# NST-28037B.net
KiCad netlist of a schematic drawn in EAGLE
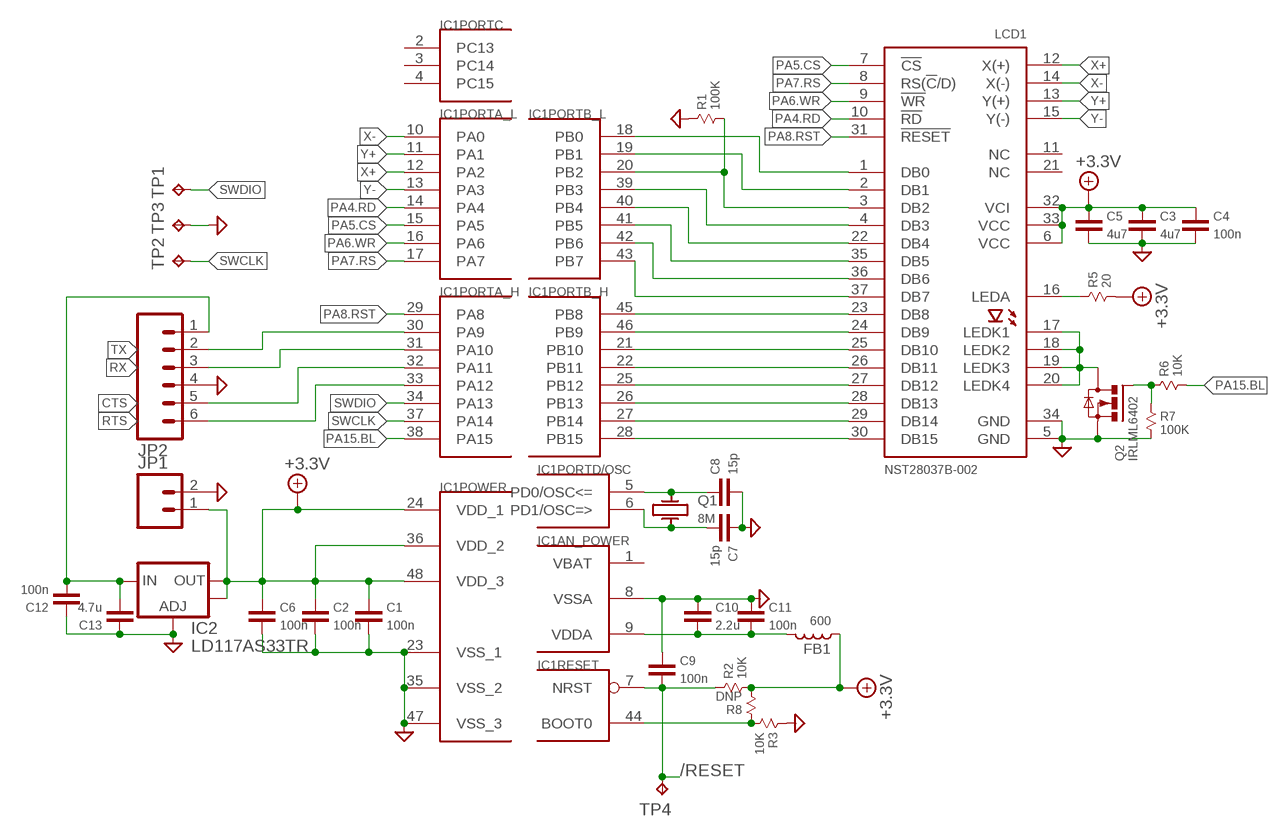
[diagram p0: schematic, sheet 1]

(export (version "E")
  (design (tool "Eeschema 10.0.6"))
  (components
    (comp (ref "C1")
      (value "100n")
      (footprint "eagle-import:0603")
      (libsource (lib "eagle-import") (part "CAP-0603"))
    )
    (comp (ref "C2")
      (value "100n")
      (footprint "eagle-import:0603")
      (libsource (lib "eagle-import") (part "CAP-0603"))
    )
    (comp (ref "C3")
      (value "4u7")
      (footprint "eagle-import:0603")
      (libsource (lib "eagle-import") (part "CAP-0603"))
    )
    (comp (ref "C4")
      (value "100n")
      (footprint "eagle-import:0603")
      (libsource (lib "eagle-import") (part "CAP-0603"))
    )
    (comp (ref "C5")
      (value "4u7")
      (footprint "eagle-import:0603")
      (libsource (lib "eagle-import") (part "CAP-0603"))
    )
    (comp (ref "C6")
      (value "100n")
      (footprint "eagle-import:0603")
      (libsource (lib "eagle-import") (part "CAP-0603"))
    )
    (comp (ref "C7")
      (value "15p")
      (footprint "eagle-import:0603")
      (libsource (lib "eagle-import") (part "CAP-0603"))
    )
    (comp (ref "C8")
      (value "15p")
      (footprint "eagle-import:0603")
      (libsource (lib "eagle-import") (part "CAP-0603"))
    )
    (comp (ref "C9")
      (value "100n")
      (footprint "eagle-import:0603")
      (libsource (lib "eagle-import") (part "CAP-0603"))
    )
    (comp (ref "C10")
      (value "2.2u")
      (footprint "eagle-import:0603")
      (libsource (lib "eagle-import") (part "CAP-0603"))
    )
    (comp (ref "C11")
      (value "100n")
      (footprint "eagle-import:0603")
      (libsource (lib "eagle-import") (part "CAP-0603"))
    )
    (comp (ref "C12")
      (value "100n")
      (footprint "eagle-import:0603")
      (libsource (lib "eagle-import") (part "CAP-0603"))
    )
    (comp (ref "C13")
      (value "4.7u")
      (footprint "eagle-import:0603")
      (libsource (lib "eagle-import") (part "CAP-0603"))
    )
    (comp (ref "FB1")
      (value "600")
      (footprint "eagle-import:0603")
      (libsource (lib "eagle-import") (part "INDUCTOR-0603"))
    )
    (comp (ref "IC1")
      (value "STM32F10XCXT6")
      (footprint "eagle-import:TQFP48")
      (libsource (lib "eagle-import") (part "STM32F10XCXT6"))
    )
    (comp (ref "IC2")
      (value "LD117AS33TR")
      (footprint "eagle-import:SOT223")
      (libsource (lib "eagle-import") (part "LD117A?S33TR"))
    )
    (comp (ref "JP1")
      (value "M02PTH")
      (footprint "eagle-import:1X02")
      (libsource (lib "eagle-import") (part "M02PTH"))
    )
    (comp (ref "JP2")
      (value "M06SIP")
      (footprint "eagle-import:1X06")
      (libsource (lib "eagle-import") (part "M06SIP"))
    )
    (comp (ref "LCD1")
      (value "NST28037B-002")
      (footprint "eagle-import:NST28037B-002")
      (libsource (lib "eagle-import") (part "NST28037B-002"))
    )
    (comp (ref "Q1")
      (value "8M")
      (footprint "eagle-import:KX-9A")
      (libsource (lib "eagle-import") (part "CRYSTAL-KX-9A"))
    )
    (comp (ref "Q2")
      (value "IRLML6402")
      (footprint "eagle-import:SOT-23")
      (libsource (lib "eagle-import") (part "MOSFET-N-SOT23"))
    )
    (comp (ref "R1")
      (value "100K")
      (footprint "eagle-import:0603")
      (libsource (lib "eagle-import") (part "RESISTOR-0603"))
    )
    (comp (ref "R2")
      (value "10K")
      (footprint "eagle-import:0603")
      (libsource (lib "eagle-import") (part "RESISTOR-0603"))
    )
    (comp (ref "R3")
      (value "10K")
      (footprint "eagle-import:0603")
      (libsource (lib "eagle-import") (part "RESISTOR-0603"))
    )
    (comp (ref "R5")
      (value "20")
      (footprint "eagle-import:0805")
      (libsource (lib "eagle-import") (part "RESISTOR-0805"))
    )
    (comp (ref "R6")
      (value "10K")
      (footprint "eagle-import:0603")
      (libsource (lib "eagle-import") (part "RESISTOR-0603"))
    )
    (comp (ref "R7")
      (value "100K")
      (footprint "eagle-import:0603")
      (libsource (lib "eagle-import") (part "RESISTOR-0603"))
    )
    (comp (ref "R8")
      (value "DNP")
      (footprint "eagle-import:0603")
      (libsource (lib "eagle-import") (part "RESISTOR-0603"))
    )
    (comp (ref "TP1")
      (value "TPTP12R")
      (footprint "eagle-import:TP12R")
      (libsource (lib "eagle-import") (part "TPTP12R"))
    )
    (comp (ref "TP2")
      (value "TPTP12R")
      (footprint "eagle-import:TP12R")
      (libsource (lib "eagle-import") (part "TPTP12R"))
    )
    (comp (ref "TP3")
      (value "TPTP12R")
      (footprint "eagle-import:TP12R")
      (libsource (lib "eagle-import") (part "TPTP12R"))
    )
    (comp (ref "TP4")
      (value "TPTP12R")
      (footprint "eagle-import:TP12R")
      (libsource (lib "eagle-import") (part "TPTP12R"))
    )
  )
  (nets
    (net (code "1") (name "+3.3V") (class "Default")
      (node (ref "C1") (pin "2") (pinfunction "2_2") (pintype "passive"))
      (node (ref "C2") (pin "2") (pinfunction "2_2") (pintype "passive"))
      (node (ref "C3") (pin "2") (pinfunction "2_2") (pintype "passive"))
      (node (ref "C4") (pin "2") (pinfunction "2_2") (pintype "passive"))
      (node (ref "C5") (pin "2") (pinfunction "2_2") (pintype "passive"))
      (node (ref "C6") (pin "2") (pinfunction "2_2") (pintype "passive"))
      (node (ref "FB1") (pin "1") (pinfunction "1_1") (pintype "passive"))
      (node (ref "IC1") (pin "24") (pinfunction "VDD_1_24") (pintype "power_in"))
      (node (ref "IC1") (pin "36") (pinfunction "VDD_2_36") (pintype "power_in"))
      (node (ref "IC1") (pin "48") (pinfunction "VDD_3_48") (pintype "power_in"))
      (node (ref "IC2") (pin "2") (pinfunction "OUT_2") (pintype "passive"))
      (node (ref "IC2") (pin "4") (pinfunction "OUT_4") (pintype "passive"))
      (node (ref "JP1") (pin "1") (pinfunction "1_1") (pintype "passive"))
      (node (ref "LCD1") (pin "32") (pinfunction "VCI_32") (pintype "power_in"))
      (node (ref "LCD1") (pin "33") (pinfunction "VCC_33") (pintype "power_in"))
      (node (ref "LCD1") (pin "6") (pinfunction "VCC_6") (pintype "power_in"))
      (node (ref "R2") (pin "2") (pinfunction "2_2") (pintype "passive"))
      (node (ref "R5") (pin "2") (pinfunction "2_2") (pintype "passive"))
      (node (ref "R8") (pin "2") (pinfunction "2_2") (pintype "passive"))
    )
    (net (code "2") (name "/VBAT") (class "Default")
      (node (ref "IC1") (pin "1") (pinfunction "VBAT_1") (pintype "power_in"))
    )
    (net (code "3") (name "/{slash}RESET") (class "Default")
      (node (ref "C9") (pin "1") (pinfunction "1_1") (pintype "passive"))
      (node (ref "IC1") (pin "7") (pinfunction "NRST_7") (pintype "input"))
      (node (ref "R2") (pin "1") (pinfunction "1_1") (pintype "passive"))
      (node (ref "TP4") (pin "TP") (pinfunction "TP_TP") (pintype "input"))
    )
    (net (code "4") (name "CTS") (class "Default")
      (node (ref "IC1") (pin "32") (pinfunction "PA11_32") (pintype "bidirectional"))
      (node (ref "JP2") (pin "5") (pinfunction "5_5") (pintype "passive"))
    )
    (net (code "5") (name "GND") (class "Default")
      (node (ref "C1") (pin "1") (pinfunction "1_1") (pintype "passive"))
      (node (ref "C10") (pin "2") (pinfunction "2_2") (pintype "passive"))
      (node (ref "C11") (pin "2") (pinfunction "2_2") (pintype "passive"))
      (node (ref "C12") (pin "2") (pinfunction "2_2") (pintype "passive"))
      (node (ref "C13") (pin "2") (pinfunction "2_2") (pintype "passive"))
      (node (ref "C2") (pin "1") (pinfunction "1_1") (pintype "passive"))
      (node (ref "C3") (pin "1") (pinfunction "1_1") (pintype "passive"))
      (node (ref "C4") (pin "1") (pinfunction "1_1") (pintype "passive"))
      (node (ref "C5") (pin "1") (pinfunction "1_1") (pintype "passive"))
      (node (ref "C6") (pin "1") (pinfunction "1_1") (pintype "passive"))
      (node (ref "C7") (pin "2") (pinfunction "2_2") (pintype "passive"))
      (node (ref "C8") (pin "1") (pinfunction "1_1") (pintype "passive"))
      (node (ref "C9") (pin "2") (pinfunction "2_2") (pintype "passive"))
      (node (ref "IC1") (pin "23") (pinfunction "VSS_1_23") (pintype "power_in"))
      (node (ref "IC1") (pin "35") (pinfunction "VSS_2_35") (pintype "power_in"))
      (node (ref "IC1") (pin "47") (pinfunction "VSS_3_47") (pintype "power_in"))
      (node (ref "IC1") (pin "8") (pinfunction "VSSA_8") (pintype "power_in"))
      (node (ref "IC2") (pin "1") (pinfunction "ADJ_1") (pintype "input"))
      (node (ref "JP1") (pin "2") (pinfunction "2_2") (pintype "passive"))
      (node (ref "JP2") (pin "4") (pinfunction "4_4") (pintype "passive"))
      (node (ref "LCD1") (pin "34") (pinfunction "GND_34") (pintype "power_in"))
      (node (ref "LCD1") (pin "5") (pinfunction "GND_5") (pintype "power_in"))
      (node (ref "Q2") (pin "2") (pinfunction "S_2") (pintype "passive"))
      (node (ref "R1") (pin "1") (pinfunction "1_1") (pintype "passive"))
      (node (ref "R3") (pin "1") (pinfunction "1_1") (pintype "passive"))
      (node (ref "R7") (pin "2") (pinfunction "2_2") (pintype "passive"))
      (node (ref "TP3") (pin "TP") (pinfunction "TP_TP") (pintype "input"))
    )
    (net (code "6") (name "Net-(IC1A-VDDA)") (class "Default")
      (node (ref "C10") (pin "1") (pinfunction "1_1") (pintype "passive"))
      (node (ref "C11") (pin "1") (pinfunction "1_1") (pintype "passive"))
      (node (ref "FB1") (pin "2") (pinfunction "2_2") (pintype "passive"))
      (node (ref "IC1") (pin "9") (pinfunction "VDDA_9") (pintype "power_in"))
    )
    (net (code "7") (name "Net-(IC1D-PB8)") (class "Default")
      (node (ref "IC1") (pin "45") (pinfunction "PB8_45") (pintype "bidirectional"))
      (node (ref "LCD1") (pin "23") (pinfunction "DB8_23") (pintype "bidirectional"))
    )
    (net (code "8") (name "Net-(IC1D-PB9)") (class "Default")
      (node (ref "IC1") (pin "46") (pinfunction "PB9_46") (pintype "bidirectional"))
      (node (ref "LCD1") (pin "24") (pinfunction "DB9_24") (pintype "bidirectional"))
    )
    (net (code "9") (name "Net-(IC1D-PB10)") (class "Default")
      (node (ref "IC1") (pin "21") (pinfunction "PB10_21") (pintype "bidirectional"))
      (node (ref "LCD1") (pin "25") (pinfunction "DB10_25") (pintype "bidirectional"))
    )
    (net (code "10") (name "Net-(IC1D-PB11)") (class "Default")
      (node (ref "IC1") (pin "22") (pinfunction "PB11_22") (pintype "bidirectional"))
      (node (ref "LCD1") (pin "26") (pinfunction "DB11_26") (pintype "bidirectional"))
    )
    (net (code "11") (name "Net-(IC1D-PB12)") (class "Default")
      (node (ref "IC1") (pin "25") (pinfunction "PB12_25") (pintype "bidirectional"))
      (node (ref "LCD1") (pin "27") (pinfunction "DB12_27") (pintype "bidirectional"))
    )
    (net (code "12") (name "Net-(IC1D-PB13)") (class "Default")
      (node (ref "IC1") (pin "26") (pinfunction "PB13_26") (pintype "bidirectional"))
      (node (ref "LCD1") (pin "28") (pinfunction "DB13_28") (pintype "bidirectional"))
    )
    (net (code "13") (name "Net-(IC1D-PB14)") (class "Default")
      (node (ref "IC1") (pin "27") (pinfunction "PB14_27") (pintype "bidirectional"))
      (node (ref "LCD1") (pin "29") (pinfunction "DB14_29") (pintype "bidirectional"))
    )
    (net (code "14") (name "Net-(IC1D-PB15)") (class "Default")
      (node (ref "IC1") (pin "28") (pinfunction "PB15_28") (pintype "bidirectional"))
      (node (ref "LCD1") (pin "30") (pinfunction "DB15_30") (pintype "bidirectional"))
    )
    (net (code "15") (name "Net-(IC1E-PB0)") (class "Default")
      (node (ref "IC1") (pin "18") (pinfunction "PB0_18") (pintype "bidirectional"))
      (node (ref "LCD1") (pin "1") (pinfunction "DB0_1") (pintype "bidirectional"))
    )
    (net (code "16") (name "Net-(IC1E-PB1)") (class "Default")
      (node (ref "IC1") (pin "19") (pinfunction "PB1_19") (pintype "bidirectional"))
      (node (ref "LCD1") (pin "2") (pinfunction "DB1_2") (pintype "bidirectional"))
    )
    (net (code "17") (name "Net-(IC1E-PB2)") (class "Default")
      (node (ref "IC1") (pin "20") (pinfunction "PB2_20") (pintype "bidirectional"))
      (node (ref "LCD1") (pin "3") (pinfunction "DB2_3") (pintype "bidirectional"))
      (node (ref "R1") (pin "2") (pinfunction "2_2") (pintype "passive"))
    )
    (net (code "18") (name "Net-(IC1E-PB3)") (class "Default")
      (node (ref "IC1") (pin "39") (pinfunction "PB3_39") (pintype "bidirectional"))
      (node (ref "LCD1") (pin "4") (pinfunction "DB3_4") (pintype "bidirectional"))
    )
    (net (code "19") (name "Net-(IC1E-PB4)") (class "Default")
      (node (ref "IC1") (pin "40") (pinfunction "PB4_40") (pintype "bidirectional"))
      (node (ref "LCD1") (pin "22") (pinfunction "DB4_22") (pintype "bidirectional"))
    )
    (net (code "20") (name "Net-(IC1E-PB5)") (class "Default")
      (node (ref "IC1") (pin "41") (pinfunction "PB5_41") (pintype "bidirectional"))
      (node (ref "LCD1") (pin "35") (pinfunction "DB5_35") (pintype "bidirectional"))
    )
    (net (code "21") (name "Net-(IC1E-PB6)") (class "Default")
      (node (ref "IC1") (pin "42") (pinfunction "PB6_42") (pintype "bidirectional"))
      (node (ref "LCD1") (pin "36") (pinfunction "DB6_36") (pintype "bidirectional"))
    )
    (net (code "22") (name "Net-(IC1E-PB7)") (class "Default")
      (node (ref "IC1") (pin "43") (pinfunction "PB7_43") (pintype "bidirectional"))
      (node (ref "LCD1") (pin "37") (pinfunction "DB7_37") (pintype "bidirectional"))
    )
    (net (code "23") (name "Net-(IC1G-PD0{slash}OSC<=)") (class "Default")
      (node (ref "C8") (pin "2") (pinfunction "2_2") (pintype "passive"))
      (node (ref "IC1") (pin "5") (pinfunction "PD0/OSC<=_5") (pintype "bidirectional"))
      (node (ref "Q1") (pin "1") (pinfunction "1_1") (pintype "passive"))
    )
    (net (code "24") (name "Net-(IC1G-PD1{slash}OSC=>)") (class "Default")
      (node (ref "C7") (pin "1") (pinfunction "1_1") (pintype "passive"))
      (node (ref "IC1") (pin "6") (pinfunction "PD1/OSC=>_6") (pintype "bidirectional"))
      (node (ref "Q1") (pin "3") (pinfunction "2_3") (pintype "passive"))
    )
    (net (code "25") (name "Net-(IC1I-BOOT0)") (class "Default")
      (node (ref "IC1") (pin "44") (pinfunction "BOOT0_44") (pintype "input"))
      (node (ref "R3") (pin "2") (pinfunction "2_2") (pintype "passive"))
      (node (ref "R8") (pin "1") (pinfunction "1_1") (pintype "passive"))
    )
    (net (code "26") (name "Net-(IC2-IN)") (class "Default")
      (node (ref "C12") (pin "1") (pinfunction "1_1") (pintype "passive"))
      (node (ref "C13") (pin "1") (pinfunction "1_1") (pintype "passive"))
      (node (ref "IC2") (pin "3") (pinfunction "IN_3") (pintype "input"))
      (node (ref "JP2") (pin "1") (pinfunction "1_1") (pintype "passive"))
    )
    (net (code "27") (name "Net-(LCD1-LEDA)") (class "Default")
      (node (ref "LCD1") (pin "16") (pinfunction "LEDA_16") (pintype "passive"))
      (node (ref "R5") (pin "1") (pinfunction "1_1") (pintype "passive"))
    )
    (net (code "28") (name "Net-(LCD1-LEDK1)") (class "Default")
      (node (ref "LCD1") (pin "17") (pinfunction "LEDK1_17") (pintype "passive"))
      (node (ref "LCD1") (pin "18") (pinfunction "LEDK2_18") (pintype "passive"))
      (node (ref "LCD1") (pin "19") (pinfunction "LEDK3_19") (pintype "passive"))
      (node (ref "LCD1") (pin "20") (pinfunction "LEDK4_20") (pintype "passive"))
      (node (ref "Q2") (pin "3") (pinfunction "D_3") (pintype "passive"))
    )
    (net (code "29") (name "Net-(Q2-G)") (class "Default")
      (node (ref "Q2") (pin "1") (pinfunction "G_1") (pintype "passive"))
      (node (ref "R6") (pin "1") (pinfunction "1_1") (pintype "passive"))
      (node (ref "R7") (pin "1") (pinfunction "1_1") (pintype "passive"))
    )
    (net (code "30") (name "PA4.RD") (class "Default")
      (node (ref "IC1") (pin "14") (pinfunction "PA4_14") (pintype "bidirectional"))
      (node (ref "LCD1") (pin "10") (pinfunction "~{RD}_10") (pintype "input"))
    )
    (net (code "31") (name "PA5.CS") (class "Default")
      (node (ref "IC1") (pin "15") (pinfunction "PA5_15") (pintype "bidirectional"))
      (node (ref "LCD1") (pin "7") (pinfunction "~{CS}_7") (pintype "input"))
    )
    (net (code "32") (name "PA6.WR") (class "Default")
      (node (ref "IC1") (pin "16") (pinfunction "PA6_16") (pintype "bidirectional"))
      (node (ref "LCD1") (pin "9") (pinfunction "~{WR}_9") (pintype "input"))
    )
    (net (code "33") (name "PA7.RS") (class "Default")
      (node (ref "IC1") (pin "17") (pinfunction "PA7_17") (pintype "bidirectional"))
      (node (ref "LCD1") (pin "8") (pinfunction "RS(~{C}/D)_8") (pintype "input"))
    )
    (net (code "34") (name "PA8.RST") (class "Default")
      (node (ref "IC1") (pin "29") (pinfunction "PA8_29") (pintype "bidirectional"))
      (node (ref "LCD1") (pin "31") (pinfunction "~{RESET}_31") (pintype "input"))
    )
    (net (code "35") (name "PA15.BL") (class "Default")
      (node (ref "IC1") (pin "38") (pinfunction "PA15_38") (pintype "bidirectional"))
      (node (ref "R6") (pin "2") (pinfunction "2_2") (pintype "passive"))
    )
    (net (code "36") (name "RTS") (class "Default")
      (node (ref "IC1") (pin "33") (pinfunction "PA12_33") (pintype "bidirectional"))
      (node (ref "JP2") (pin "6") (pinfunction "6_6") (pintype "passive"))
    )
    (net (code "37") (name "RX") (class "Default")
      (node (ref "IC1") (pin "31") (pinfunction "PA10_31") (pintype "bidirectional"))
      (node (ref "JP2") (pin "3") (pinfunction "3_3") (pintype "passive"))
    )
    (net (code "38") (name "SWCLK") (class "Default")
      (node (ref "IC1") (pin "37") (pinfunction "PA14_37") (pintype "bidirectional"))
      (node (ref "TP2") (pin "TP") (pinfunction "TP_TP") (pintype "input"))
    )
    (net (code "39") (name "SWDIO") (class "Default")
      (node (ref "IC1") (pin "34") (pinfunction "PA13_34") (pintype "bidirectional"))
      (node (ref "TP1") (pin "TP") (pinfunction "TP_TP") (pintype "input"))
    )
    (net (code "40") (name "TX") (class "Default")
      (node (ref "IC1") (pin "30") (pinfunction "PA9_30") (pintype "bidirectional"))
      (node (ref "JP2") (pin "2") (pinfunction "2_2") (pintype "passive"))
    )
    (net (code "41") (name "X+") (class "Default")
      (node (ref "IC1") (pin "12") (pinfunction "PA2_12") (pintype "bidirectional"))
      (node (ref "LCD1") (pin "12") (pinfunction "X(+)_12") (pintype "passive"))
    )
    (net (code "42") (name "X-") (class "Default")
      (node (ref "IC1") (pin "10") (pinfunction "PA0_10") (pintype "bidirectional"))
      (node (ref "LCD1") (pin "14") (pinfunction "X(-)_14") (pintype "passive"))
    )
    (net (code "43") (name "Y+") (class "Default")
      (node (ref "IC1") (pin "11") (pinfunction "PA1_11") (pintype "bidirectional"))
      (node (ref "LCD1") (pin "13") (pinfunction "Y(+)_13") (pintype "passive"))
    )
    (net (code "44") (name "Y-") (class "Default")
      (node (ref "IC1") (pin "13") (pinfunction "PA3_13") (pintype "bidirectional"))
      (node (ref "LCD1") (pin "15") (pinfunction "Y(-)_15") (pintype "passive"))
    )
    (net (code "45") (name "unconnected-(IC1F-PC13-Pad2)") (class "Default")
      (node (ref "IC1") (pin "2") (pinfunction "PC13_2") (pintype "bidirectional"))
    )
    (net (code "46") (name "unconnected-(IC1F-PC14-Pad3)") (class "Default")
      (node (ref "IC1") (pin "3") (pinfunction "PC14_3") (pintype "bidirectional"))
    )
    (net (code "47") (name "unconnected-(IC1F-PC15-Pad4)") (class "Default")
      (node (ref "IC1") (pin "4") (pinfunction "PC15_4") (pintype "bidirectional"))
    )
    (net (code "48") (name "unconnected-(LCD1-NC-Pad11)") (class "Default")
      (node (ref "LCD1") (pin "11") (pinfunction "NC_11") (pintype "no_connect"))
    )
    (net (code "49") (name "unconnected-(LCD1-NC-Pad21)") (class "Default")
      (node (ref "LCD1") (pin "21") (pinfunction "NC_21") (pintype "no_connect"))
    )
  )
)
